# Microcontroller.net
KiCad netlist of a schematic drawn in Altium Designer
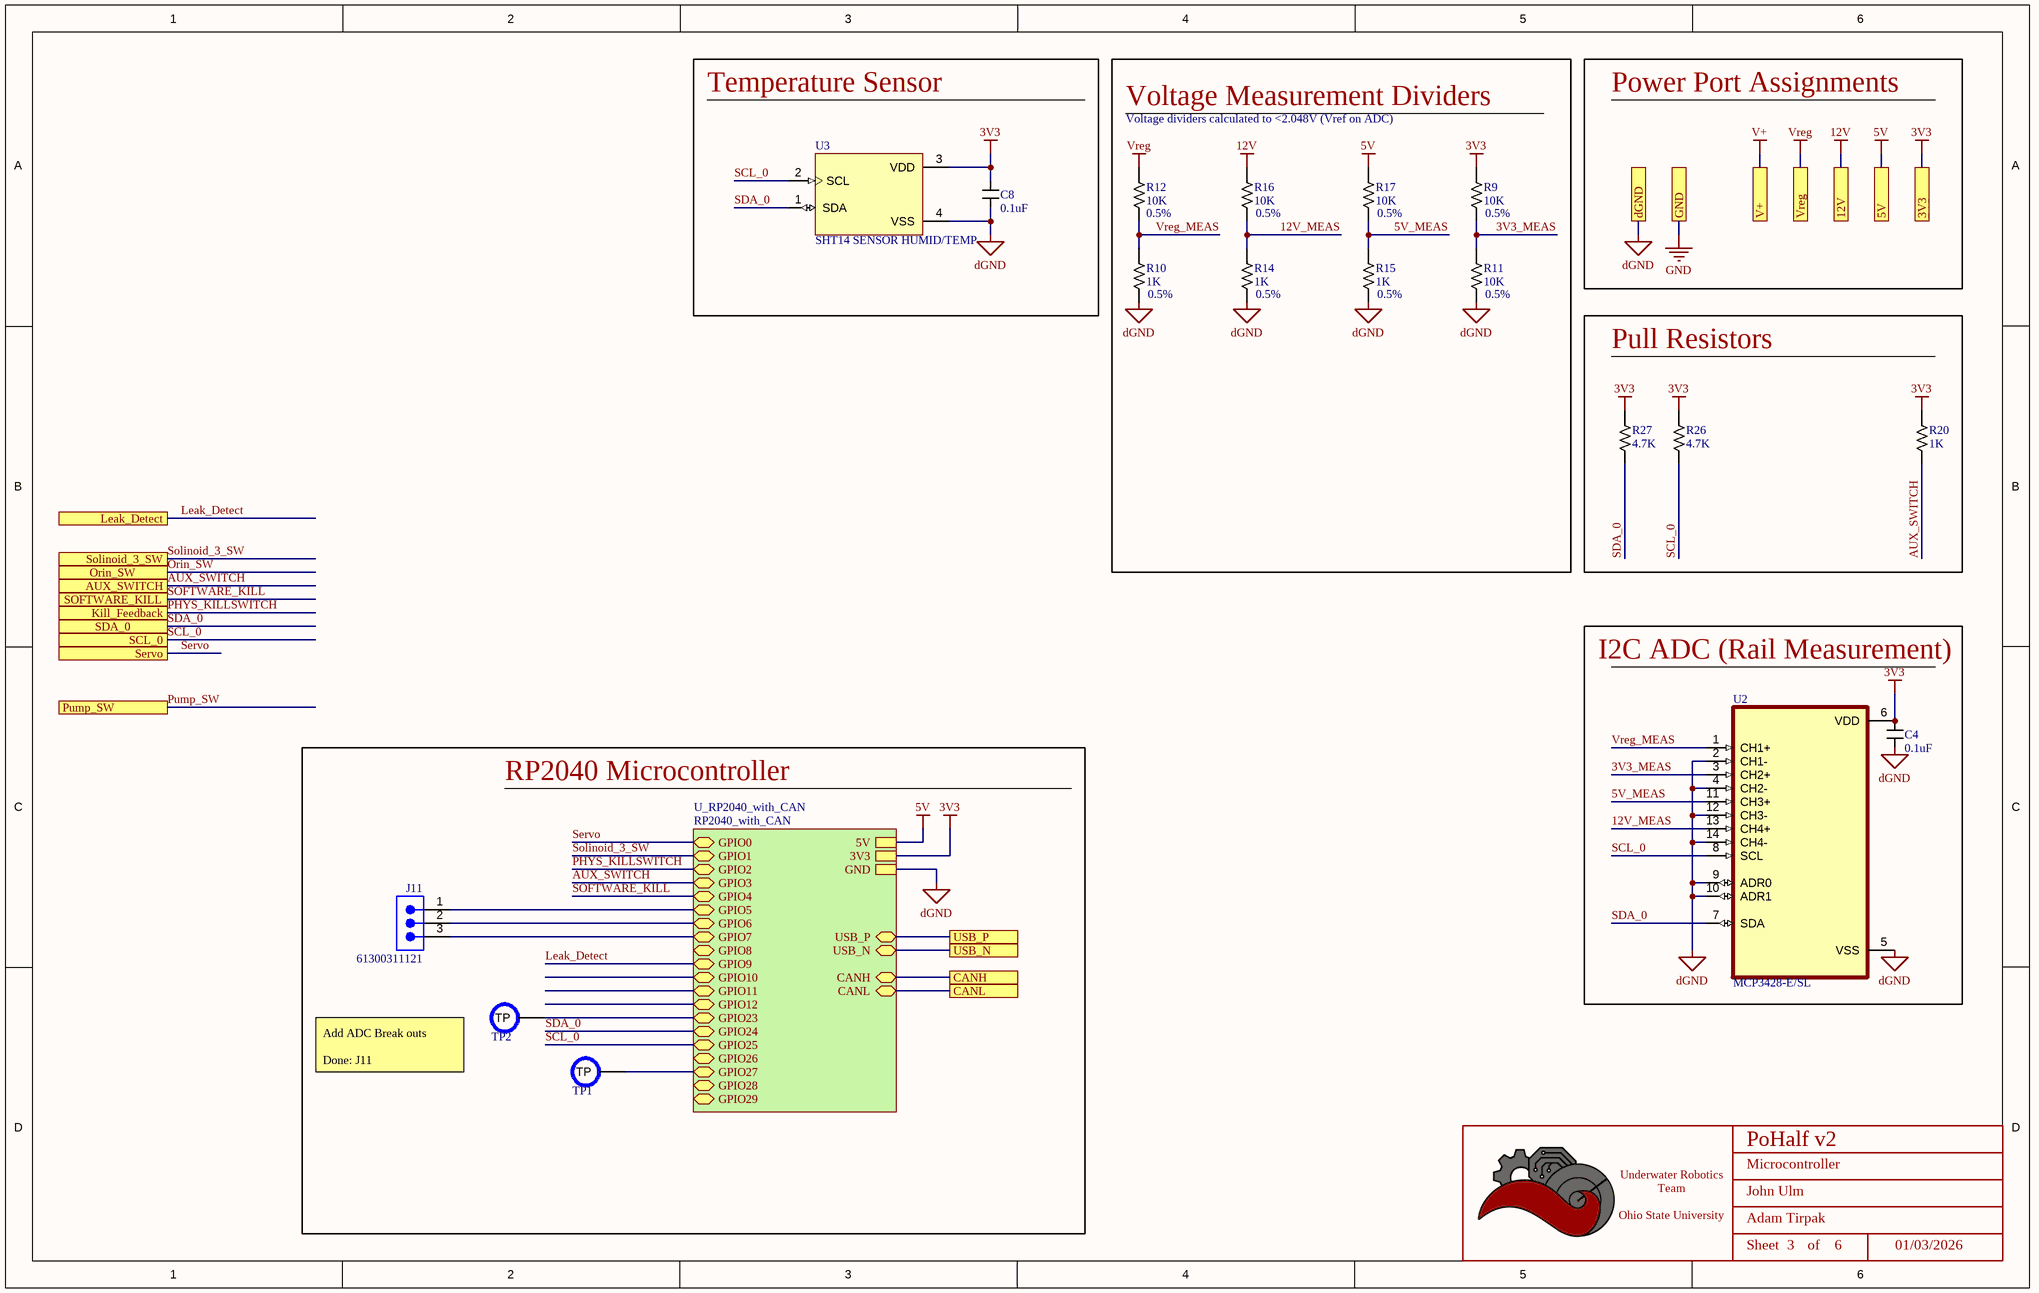
[diagram p0: Microcontroller.SchDoc]

(export (version "E")
  (design (tool "Eeschema 10.0.6"))
  (components
    (comp (ref "C4")
      (value "0.1uF")
      (footprint "CAPACITOR_0603")
      (description "Cap 100nF 6.3V +/-10%\r\nCeramic 0603")
      (fields
        (field (name "TOLERANCE") "+/- 10%")
        (field (name "VOLTAGE") "6.3V")
        (field (name "MADE BY") "Flip B")
      )
      (libsource (lib "Capacitors") (part "CAPACITOR_0.1uF_0603"))
    )
    (comp (ref "C8")
      (value "0.1uF")
      (footprint "CAPACITOR_0603")
      (description "Cap 100nF 6.3V +/-10%\r\nCeramic 0603")
      (fields
        (field (name "TOLERANCE") "+/- 10%")
        (field (name "VOLTAGE") "6.3V")
        (field (name "MADE BY") "Flip B")
      )
      (libsource (lib "Capacitors") (part "CAPACITOR_0.1uF_0603"))
    )
    (comp (ref "J11")
      (value "61300311121")
      (footprint "61300311121")
      (description "THT Vertical Pin Header WR-PHD, Pitch 2.54 mm, Single Row, 3 pins")
      (libsource (lib "Altium Content Vault") (part "Header_Male_1R_03P"))
    )
    (comp (ref "R9")
      (value "10k Ohm 0.5% 1/10W")
      (footprint "RESISTOR_0603")
      (description "RES 10k OHM 0.5% 1/10W 0603")
      (fields
        (field (name "TOLERANCE") "+/- 0.5%")
        (field (name "VALUE  (OHMS)") "10K")
        (field (name "MADE BY") "Robert Pafford")
      )
      (libsource (lib "Resistors") (part "RESISTOR_10K_0.5%_0603"))
    )
    (comp (ref "R10")
      (value "1k Ohm 5% 1/10W")
      (footprint "RESISTOR_0603")
      (description "RES 1k OHM 0.5% 1/10W 0603")
      (fields
        (field (name "TOLERANCE") "+/- 0.5%")
        (field (name "VALUE  (OHMS)") "1K")
        (field (name "MADE BY") "Robert Pafford")
      )
      (libsource (lib "Resistors") (part "RESISTOR_1K_0.5%_0603"))
    )
    (comp (ref "R11")
      (value "10k Ohm 0.5% 1/10W")
      (footprint "RESISTOR_0603")
      (description "RES 10k OHM 0.5% 1/10W 0603")
      (fields
        (field (name "TOLERANCE") "+/- 0.5%")
        (field (name "VALUE  (OHMS)") "10K")
        (field (name "MADE BY") "Robert Pafford")
      )
      (libsource (lib "Resistors") (part "RESISTOR_10K_0.5%_0603"))
    )
    (comp (ref "R12")
      (value "10k Ohm 0.5% 1/10W")
      (footprint "RESISTOR_0603")
      (description "RES 10k OHM 0.5% 1/10W 0603")
      (fields
        (field (name "TOLERANCE") "+/- 0.5%")
        (field (name "VALUE  (OHMS)") "10K")
        (field (name "MADE BY") "Robert Pafford")
      )
      (libsource (lib "Resistors") (part "RESISTOR_10K_0.5%_0603"))
    )
    (comp (ref "R14")
      (value "1k Ohm 5% 1/10W")
      (footprint "RESISTOR_0603")
      (description "RES 1k OHM 0.5% 1/10W 0603")
      (fields
        (field (name "TOLERANCE") "+/- 0.5%")
        (field (name "VALUE  (OHMS)") "1K")
        (field (name "MADE BY") "Robert Pafford")
      )
      (libsource (lib "Resistors") (part "RESISTOR_1K_0.5%_0603"))
    )
    (comp (ref "R15")
      (value "1k Ohm 5% 1/10W")
      (footprint "RESISTOR_0603")
      (description "RES 1k OHM 0.5% 1/10W 0603")
      (fields
        (field (name "TOLERANCE") "+/- 0.5%")
        (field (name "VALUE  (OHMS)") "1K")
        (field (name "MADE BY") "Robert Pafford")
      )
      (libsource (lib "Resistors") (part "RESISTOR_1K_0.5%_0603"))
    )
    (comp (ref "R16")
      (value "10k Ohm 0.5% 1/10W")
      (footprint "RESISTOR_0603")
      (description "RES 10k OHM 0.5% 1/10W 0603")
      (fields
        (field (name "TOLERANCE") "+/- 0.5%")
        (field (name "VALUE  (OHMS)") "10K")
        (field (name "MADE BY") "Robert Pafford")
      )
      (libsource (lib "Resistors") (part "RESISTOR_10K_0.5%_0603"))
    )
    (comp (ref "R17")
      (value "10k Ohm 0.5% 1/10W")
      (footprint "RESISTOR_0603")
      (description "RES 10k OHM 0.5% 1/10W 0603")
      (fields
        (field (name "TOLERANCE") "+/- 0.5%")
        (field (name "VALUE  (OHMS)") "10K")
        (field (name "MADE BY") "Robert Pafford")
      )
      (libsource (lib "Resistors") (part "RESISTOR_10K_0.5%_0603"))
    )
    (comp (ref "R20")
      (value "1k Ohm 5% 1/8W")
      (footprint "RESISTOR_0603")
      (description "RES 1k OHM 5% 1/8W 0603")
      (fields
        (field (name "TOLERANCE") "+/- 5%")
        (field (name "VALUE  (OHMS)") "1K")
        (field (name "MADE BY") "Robert Pafford")
      )
      (libsource (lib "Resistors") (part "RESISTOR_1K_0603"))
    )
    (comp (ref "R26")
      (value "4.7k Ohm 5% 1/10W")
      (footprint "RESISTOR_0603")
      (description "RES 4.7k OHM 5% 1/10W 0603")
      (fields
        (field (name "TOLERANCE") "+/- 5%")
        (field (name "VALUE  (OHMS)") "4.7K")
        (field (name "MADE BY") "Robert Pafford")
      )
      (libsource (lib "Resistors") (part "RESISTOR_4.7K_0603"))
    )
    (comp (ref "R27")
      (value "4.7k Ohm 5% 1/10W")
      (footprint "RESISTOR_0603")
      (description "RES 4.7k OHM 5% 1/10W 0603")
      (fields
        (field (name "TOLERANCE") "+/- 5%")
        (field (name "VALUE  (OHMS)") "4.7K")
        (field (name "MADE BY") "Robert Pafford")
      )
      (libsource (lib "Resistors") (part "RESISTOR_4.7K_0603"))
    )
    (comp (ref "TP1")
      (value "PCB Test Point")
      (footprint "TESTPOINT_1.2MM")
      (fields (field (name "MADE BY") "Robert Pafford"))
      (libsource (lib "Connectors") (part "TESTPOINT"))
    )
    (comp (ref "TP2")
      (value "PCB Test Point")
      (footprint "TESTPOINT_1.2MM")
      (fields (field (name "MADE BY") "Robert Pafford"))
      (libsource (lib "Connectors") (part "TESTPOINT"))
    )
    (comp (ref "U2")
      (value "MCP3428-E/SL")
      (footprint "SOIC127P600X175-14N")
      (description "16 Bit Analog to Digital Converter 4 Input 1 Sigma-Delta 14-SOIC")
      (fields (field (name "MF") "Microchip"))
      (libsource (lib "MCP3428-E_SL") (part "MCP3428-E/SL"))
    )
    (comp (ref "U3")
      (value "SHT14 SENSOR HUMID/TEMP")
      (footprint "XDCR_SHT41-AD1B-R2")
      (description "Digital Relative Humidity Temperature Sensor, Â±1.8 / max 2.5 %RH, Â±0.2 Â°C, Ultra-Low-Power")
      (fields (field (name "MP") "SHT41-AD1B-R2") (field (name "MF") "Sensirion"))
      (libsource (lib "Integrated Circuits") (part "SHT41-AD1B-R2"))
    )
  )
  (nets
    (net (code "1") (name "/3V3_MEAS") (class "Default")
      (node (ref "R11") (pin "1") (pinfunction "1_1") (pintype "passive"))
      (node (ref "R9") (pin "2") (pinfunction "2_2") (pintype "passive"))
      (node (ref "U2") (pin "3") (pinfunction "CH2+_3") (pintype "input"))
    )
    (net (code "2") (name "/5V_MEAS") (class "Default")
      (node (ref "R15") (pin "1") (pinfunction "1_1") (pintype "passive"))
      (node (ref "R17") (pin "2") (pinfunction "2_2") (pintype "passive"))
      (node (ref "U2") (pin "11") (pinfunction "CH3+_11") (pintype "input"))
    )
    (net (code "3") (name "/12V_MEAS") (class "Default")
      (node (ref "R14") (pin "1") (pinfunction "1_1") (pintype "passive"))
      (node (ref "R16") (pin "2") (pinfunction "2_2") (pintype "passive"))
      (node (ref "U2") (pin "13") (pinfunction "CH4+_13") (pintype "input"))
    )
    (net (code "4") (name "/AUX_SWITCH") (class "Default")
      (node (ref "R20") (pin "2") (pinfunction "2_2") (pintype "passive"))
    )
    (net (code "7") (name "/GPIO5") (class "Default")
      (node (ref "J11") (pin "1") (pinfunction "1_1") (pintype "passive"))
    )
    (net (code "8") (name "/GPIO6") (class "Default")
      (node (ref "J11") (pin "2") (pinfunction "2_2") (pintype "passive"))
    )
    (net (code "9") (name "/GPIO7") (class "Default")
      (node (ref "J11") (pin "3") (pinfunction "3_3") (pintype "passive"))
    )
    (net (code "14") (name "/GPIO23") (class "Default")
      (node (ref "TP2") (pin "TP") (pinfunction "TP_TP") (pintype "passive"))
    )
    (net (code "16") (name "/GPIO27") (class "Default")
      (node (ref "TP1") (pin "TP") (pinfunction "TP_TP") (pintype "passive"))
    )
    (net (code "23") (name "/SCL_0") (class "Default")
      (node (ref "R26") (pin "2") (pinfunction "2_2") (pintype "passive"))
      (node (ref "U2") (pin "8") (pinfunction "SCL_8") (pintype "input"))
      (node (ref "U3") (pin "2") (pinfunction "SCL_2") (pintype "input"))
    )
    (net (code "24") (name "/SDA_0") (class "Default")
      (node (ref "R27") (pin "2") (pinfunction "2_2") (pintype "passive"))
      (node (ref "U2") (pin "7") (pinfunction "SDA_7") (pintype "bidirectional"))
      (node (ref "U3") (pin "1") (pinfunction "SDA_1") (pintype "bidirectional"))
    )
    (net (code "30") (name "/Vreg_MEAS") (class "Default")
      (node (ref "R10") (pin "1") (pinfunction "1_1") (pintype "passive"))
      (node (ref "R12") (pin "2") (pinfunction "2_2") (pintype "passive"))
      (node (ref "U2") (pin "1") (pinfunction "CH1+_1") (pintype "input"))
    )
    (net (code "31") (name "3V3") (class "Default")
      (node (ref "C4") (pin "1") (pinfunction "1_1") (pintype "passive"))
      (node (ref "C8") (pin "1") (pinfunction "1_1") (pintype "passive"))
      (node (ref "R20") (pin "1") (pinfunction "1_1") (pintype "passive"))
      (node (ref "R26") (pin "1") (pinfunction "1_1") (pintype "passive"))
      (node (ref "R27") (pin "1") (pinfunction "1_1") (pintype "passive"))
      (node (ref "R9") (pin "1") (pinfunction "1_1") (pintype "passive"))
      (node (ref "U2") (pin "6") (pinfunction "VDD_6") (pintype "power_in"))
      (node (ref "U3") (pin "3") (pinfunction "VDD_3") (pintype "power_in"))
    )
    (net (code "32") (name "5V") (class "Default")
      (node (ref "R17") (pin "1") (pinfunction "1_1") (pintype "passive"))
    )
    (net (code "33") (name "12V") (class "Default")
      (node (ref "R16") (pin "1") (pinfunction "1_1") (pintype "passive"))
    )
    (net (code "36") (name "Vreg") (class "Default")
      (node (ref "R12") (pin "1") (pinfunction "1_1") (pintype "passive"))
    )
    (net (code "37") (name "dGND") (class "Default")
      (node (ref "C4") (pin "2") (pinfunction "2_2") (pintype "passive"))
      (node (ref "C8") (pin "2") (pinfunction "2_2") (pintype "passive"))
      (node (ref "R10") (pin "2") (pinfunction "2_2") (pintype "passive"))
      (node (ref "R11") (pin "2") (pinfunction "2_2") (pintype "passive"))
      (node (ref "R14") (pin "2") (pinfunction "2_2") (pintype "passive"))
      (node (ref "R15") (pin "2") (pinfunction "2_2") (pintype "passive"))
      (node (ref "U2") (pin "10") (pinfunction "ADR1_10") (pintype "bidirectional"))
      (node (ref "U2") (pin "12") (pinfunction "CH3-_12") (pintype "input"))
      (node (ref "U2") (pin "14") (pinfunction "CH4-_14") (pintype "input"))
      (node (ref "U2") (pin "2") (pinfunction "CH1-_2") (pintype "input"))
      (node (ref "U2") (pin "4") (pinfunction "CH2-_4") (pintype "input"))
      (node (ref "U2") (pin "5") (pinfunction "VSS_5") (pintype "power_in"))
      (node (ref "U2") (pin "9") (pinfunction "ADR0_9") (pintype "bidirectional"))
      (node (ref "U3") (pin "4") (pinfunction "VSS_4") (pintype "power_in"))
    )
  )
)
